# 95_RS485_RS232.net
KiCad netlist of a schematic drawn in Altium Designer
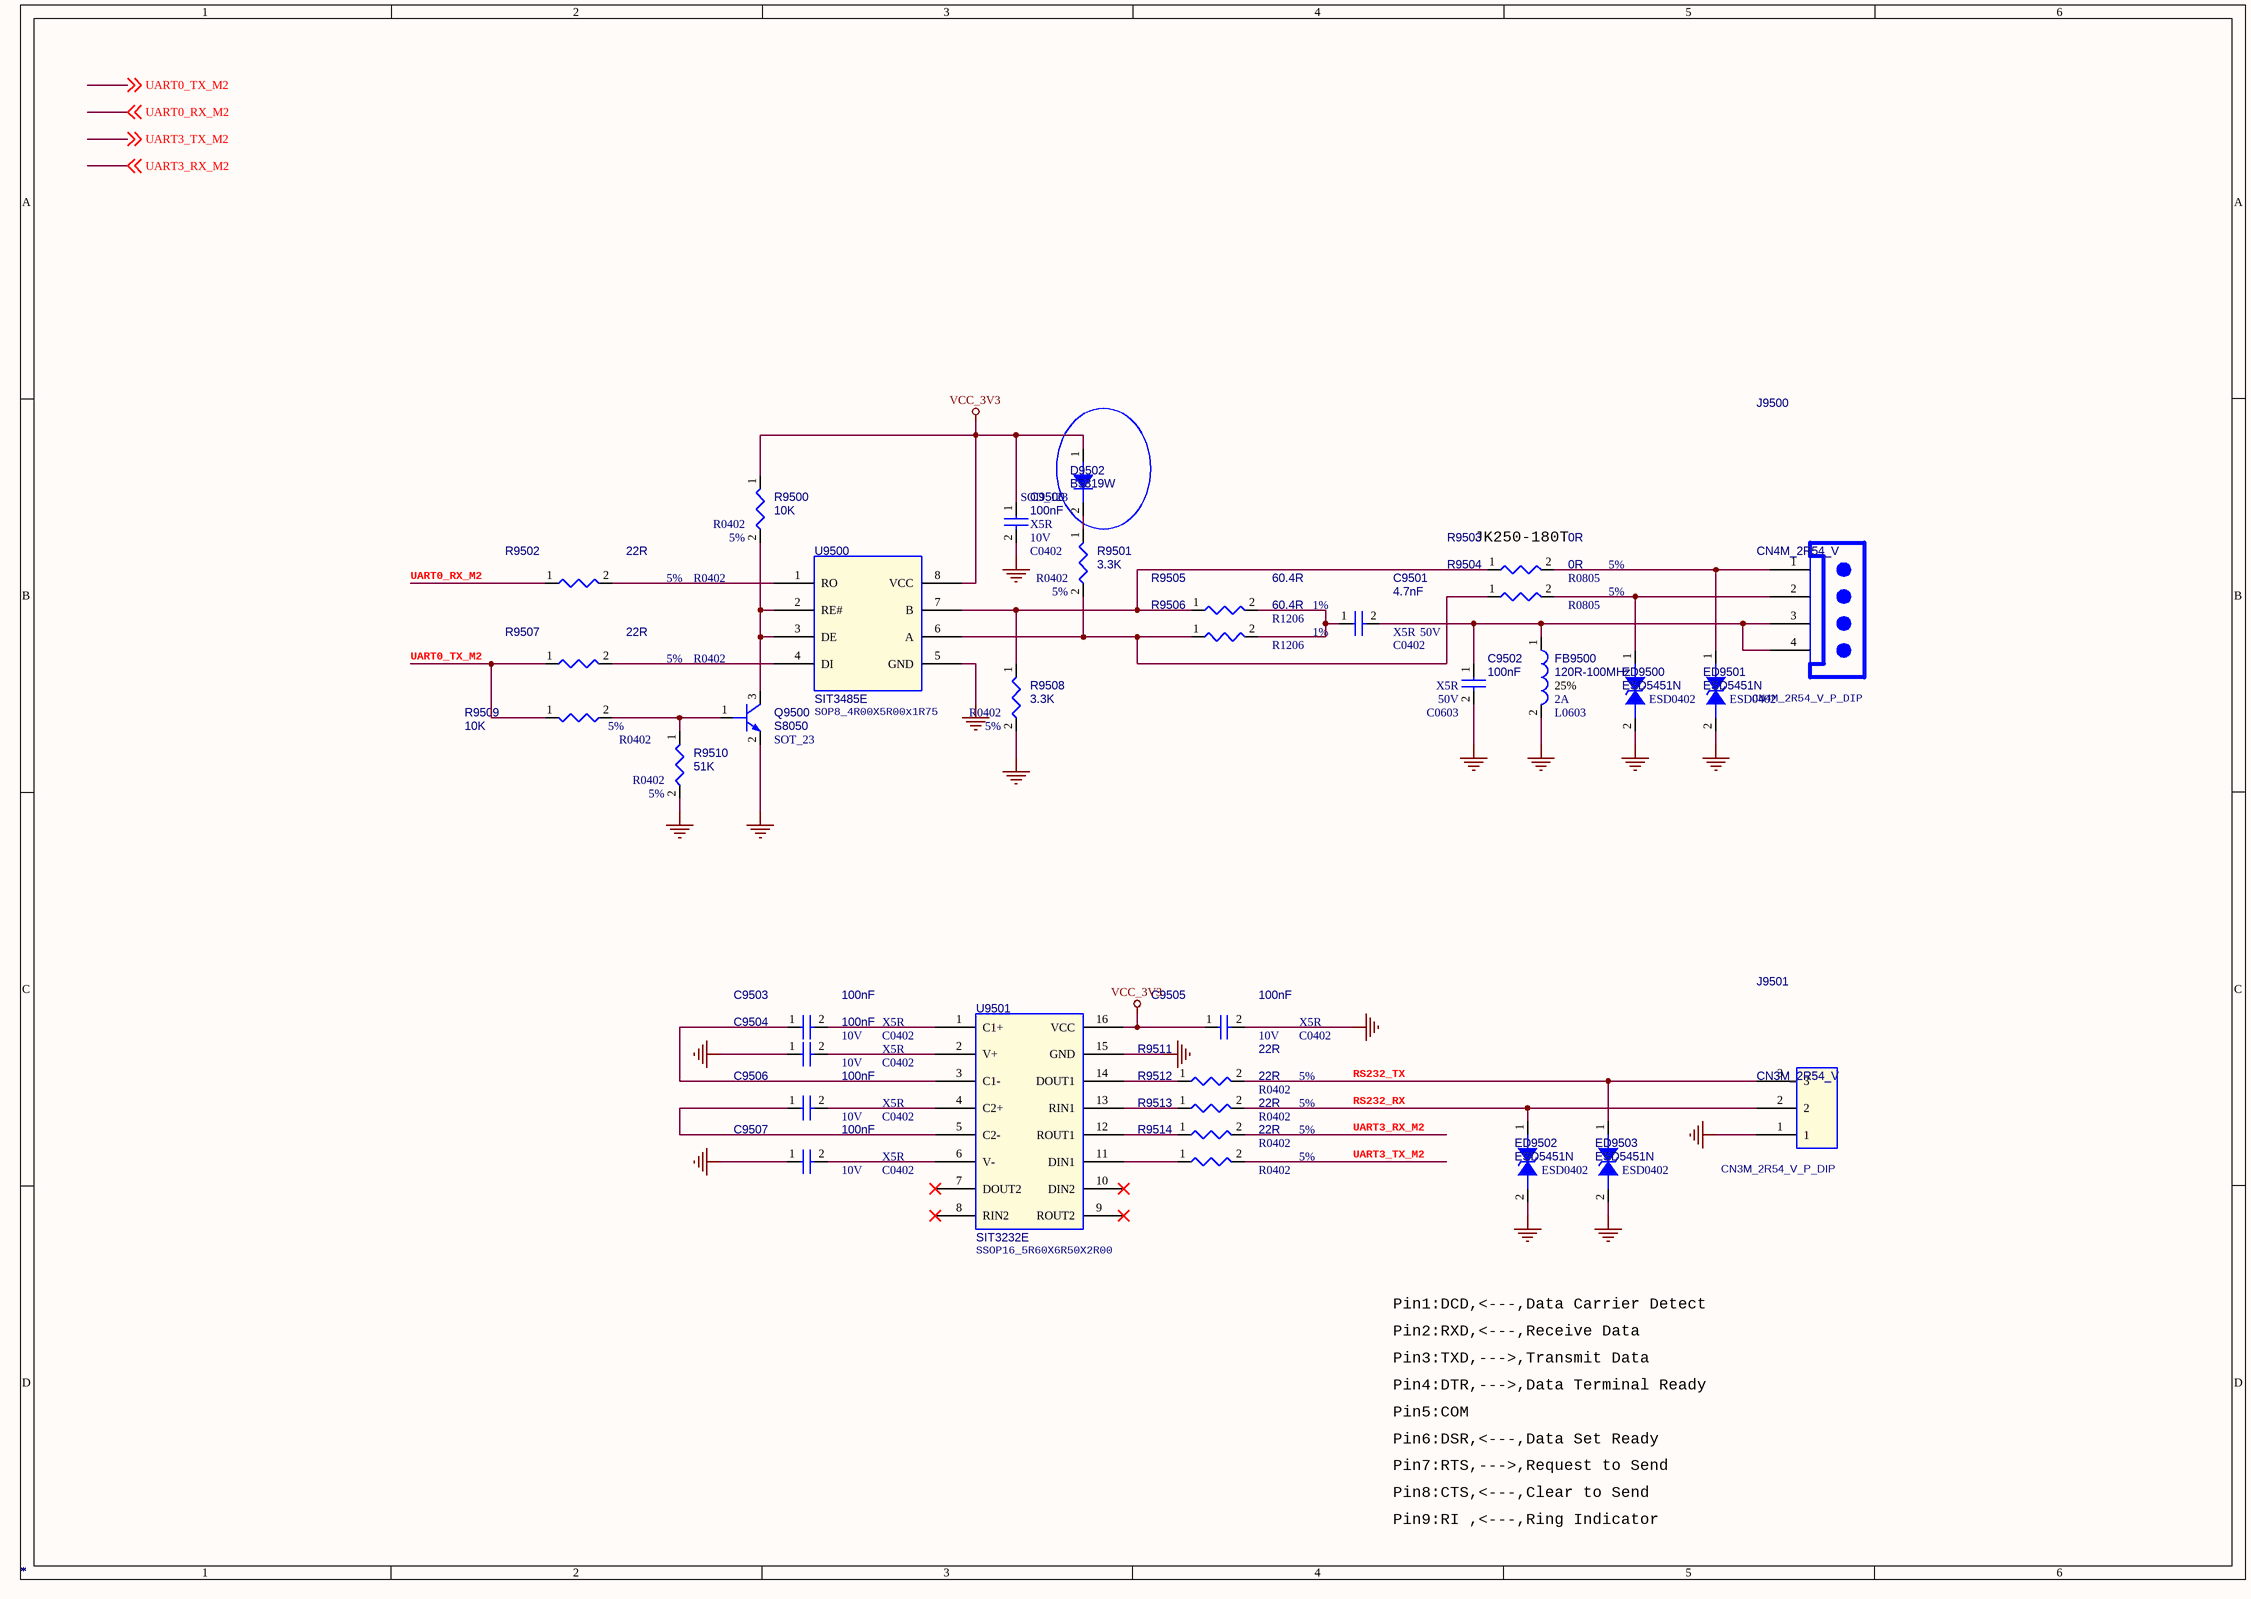
[diagram p0: 95.RS485_RS232.SchDoc]

(export (version "E")
  (design (tool "Eeschema 10.0.6"))
  (components
    (comp (ref "C9500")
      (value "*")
      (footprint "C0402")
      (description "cap,100.00nF,+/-10%,10V,X5R,C0402")
      (fields
        (field (name "VOLTAGE") "10V")
        (field (name "PCB FOOTPRINT") "C0402")
        (field (name "DIELECTRIC") "X5R")
        (field (name "MANUFACTURER") "TDK")
        (field (name "TOLERANCE") "10%")
        (field (name "ALTIUM_UNNAMED_1") "100nF")
        (field (name "CREATED BY") "JJJ")
      )
      (libsource (lib "*") (part "CAP NP"))
    )
    (comp (ref "C9501")
      (value "*")
      (footprint "C0402")
      (description "cap,4.70nF,+/-10%,50V,X5R,C0402")
      (fields
        (field (name "VOLTAGE") "50V")
        (field (name "PCB FOOTPRINT") "C0402")
        (field (name "DIELECTRIC") "X5R")
        (field (name "MANUFACTURER") "TDK")
        (field (name "TOLERANCE") "10%")
        (field (name "ALTIUM_UNNAMED_1") "4.7nF")
        (field (name "CREATED BY") "JJJ")
      )
      (libsource (lib "*") (part "CAP NP"))
    )
    (comp (ref "C9502")
      (value "*")
      (footprint "C0603")
      (description "cap,100.00nF,+/-10%,50V,X5R,C0603")
      (fields
        (field (name "VOLTAGE") "50V")
        (field (name "PCB FOOTPRINT") "C0603")
        (field (name "DIELECTRIC") "X5R")
        (field (name "TOLERANCE") "10%")
        (field (name "MANUFACTURER") "TDK")
        (field (name "ALTIUM_UNNAMED_1") "100nF")
        (field (name "CREATED BY") "JJJ")
      )
      (libsource (lib "*") (part "CAP NP"))
    )
    (comp (ref "C9503")
      (value "*")
      (footprint "C0402")
      (description "cap,100.00nF,+/-10%,10V,X5R,C0402")
      (fields
        (field (name "VOLTAGE") "10V")
        (field (name "PCB FOOTPRINT") "C0402")
        (field (name "DIELECTRIC") "X5R")
        (field (name "TOLERANCE") "10%")
        (field (name "MANUFACTURER") "TDK")
        (field (name "ALTIUM_UNNAMED_1") "100nF")
        (field (name "CREATED BY") "JJJ")
      )
      (libsource (lib "*") (part "CAP NP"))
    )
    (comp (ref "C9504")
      (value "*")
      (footprint "C0402")
      (description "cap,100.00nF,+/-10%,10V,X5R,C0402")
      (fields
        (field (name "VOLTAGE") "10V")
        (field (name "PCB FOOTPRINT") "C0402")
        (field (name "DIELECTRIC") "X5R")
        (field (name "TOLERANCE") "10%")
        (field (name "MANUFACTURER") "TDK")
        (field (name "ALTIUM_UNNAMED_1") "100nF")
        (field (name "CREATED BY") "JJJ")
      )
      (libsource (lib "*") (part "CAP NP"))
    )
    (comp (ref "C9505")
      (value "*")
      (footprint "C0402")
      (description "cap,100.00nF,+/-10%,10V,X5R,C0402")
      (fields
        (field (name "VOLTAGE") "10V")
        (field (name "PCB FOOTPRINT") "C0402")
        (field (name "DIELECTRIC") "X5R")
        (field (name "TOLERANCE") "10%")
        (field (name "MANUFACTURER") "TDK")
        (field (name "ALTIUM_UNNAMED_1") "100nF")
        (field (name "CREATED BY") "JJJ")
      )
      (libsource (lib "*") (part "CAP NP"))
    )
    (comp (ref "C9506")
      (value "*")
      (footprint "C0402")
      (description "cap,100.00nF,+/-10%,10V,X5R,C0402")
      (fields
        (field (name "VOLTAGE") "10V")
        (field (name "PCB FOOTPRINT") "C0402")
        (field (name "DIELECTRIC") "X5R")
        (field (name "TOLERANCE") "10%")
        (field (name "MANUFACTURER") "TDK")
        (field (name "ALTIUM_UNNAMED_1") "100nF")
        (field (name "CREATED BY") "JJJ")
      )
      (libsource (lib "*") (part "CAP NP"))
    )
    (comp (ref "C9507")
      (value "*")
      (footprint "C0402")
      (description "cap,100.00nF,+/-10%,10V,X5R,C0402")
      (fields
        (field (name "VOLTAGE") "10V")
        (field (name "PCB FOOTPRINT") "C0402")
        (field (name "DIELECTRIC") "X5R")
        (field (name "MANUFACTURER") "TDK")
        (field (name "TOLERANCE") "10%")
        (field (name "ALTIUM_UNNAMED_1") "100nF")
        (field (name "CREATED BY") "JJJ")
      )
      (libsource (lib "*") (part "CAP NP"))
    )
    (comp (ref "D9502")
      (value "*")
      (footprint "SOD_123")
      (description "Schottky BarrierЈ¬B5819W SOD-123")
      (fields
        (field (name "PCB FOOTPRINT") "SOD_123")
        (field (name "MANUFACTURER") "і¤µз")
        (field (name "ALTIUM_UNNAMED_1") "B5819W")
        (field (name "CREATED BY") "JJJ")
      )
      (libsource (lib "*") (part "DIODE"))
    )
    (comp (ref "ED9500")
      (value "*")
      (footprint "ESD0402")
      (description "1-Line, Bi-directional, Transient Voltage Suppressors.17.5pF.")
      (fields
        (field (name "PCB FOOTPRINT") "ESD0402")
        (field (name "MANUFACTURER") "WillSemi(О¤¶ы°лµјМе)")
        (field (name "ALTIUM_UNNAMED_1") "ESD5451N")
        (field (name "CREATED BY") "JJJ")
      )
      (libsource (lib "*") (part "DIODE BI_DIR TRIG"))
    )
    (comp (ref "ED9501")
      (value "*")
      (footprint "ESD0402")
      (description "1-Line, Bi-directional, Transient Voltage Suppressors.17.5pF.")
      (fields
        (field (name "PCB FOOTPRINT") "ESD0402")
        (field (name "MANUFACTURER") "WillSemi(О¤¶ы°лµјМе)")
        (field (name "ALTIUM_UNNAMED_1") "ESD5451N")
        (field (name "CREATED BY") "JJJ")
      )
      (libsource (lib "*") (part "DIODE BI_DIR TRIG"))
    )
    (comp (ref "ED9502")
      (value "*")
      (footprint "ESD0402")
      (description "1-Line, Bi-directional, Transient Voltage Suppressors.17.5pF.")
      (fields
        (field (name "PCB FOOTPRINT") "ESD0402")
        (field (name "MANUFACTURER") "WillSemi(О¤¶ы°лµјМе)")
        (field (name "ALTIUM_UNNAMED_1") "ESD5451N")
        (field (name "CREATED BY") "JJJ")
      )
      (libsource (lib "*") (part "DIODE BI_DIR TRIG"))
    )
    (comp (ref "ED9503")
      (value "*")
      (footprint "ESD0402")
      (description "1-Line, Bi-directional, Transient Voltage Suppressors.17.5pF.")
      (fields
        (field (name "PCB FOOTPRINT") "ESD0402")
        (field (name "MANUFACTURER") "WillSemi(О¤¶ы°лµјМе)")
        (field (name "ALTIUM_UNNAMED_1") "ESD5451N")
        (field (name "CREATED BY") "JJJ")
      )
      (libsource (lib "*") (part "DIODE BI_DIR TRIG"))
    )
    (comp (ref "FB9500")
      (value "*")
      (footprint "L0603")
      (description "BEAD,120R@100MHz,current=2000mA,0603")
      (fields
        (field (name "TOLERANCE") "25%")
        (field (name "PCB FOOTPRINT") "L0603")
        (field (name "IRMS") "2A")
        (field (name "MANUFACTURER") "Murata")
        (field (name "ALTIUM_UNNAMED_1") "120R-100MHz")
        (field (name "CREATED BY") "DZS")
      )
      (libsource (lib "*") (part "BEAD"))
    )
    (comp (ref "J9500")
      (value "*")
      (footprint "CN4M_2R54_V_P_DIP")
      (fields
        (field (name "PCB FOOTPRINT") "CN4M_2R54_V_P_DIP")
        (field (name "ALTIUM_UNNAMED_1") "CN4M_2R54_V")
      )
      (libsource (lib "*") (part "CON4_0"))
    )
    (comp (ref "J9501")
      (value "*")
      (footprint "DIP3_1X3_2R54")
      (description "µҐЕЕ3PINЈЁјдѕа2.54mmЈ©І»ґш·А»¤ЗЅµДІеХл")
      (fields
        (field (name "PCB FOOTPRINT") "CN3M_2R54_V_P_DIP")
        (field (name "MANUFACTURER PART NUMBER") "CON3M_1X3_2R54_V")
        (field (name "MANUFACTURER") "НъїЖґп")
        (field (name "ALTIUM_UNNAMED_1") "CN3M_2R54_V")
        (field (name "CREATED BY") "JJJ")
      )
      (libsource (lib "*") (part "CON3_1X3"))
    )
    (comp (ref "Q9500")
      (value "*")
      (footprint "SOT_23")
      (description "S8050,SOT23")
      (fields
        (field (name "PCB FOOTPRINT") "SOT_23")
        (field (name "MANUFACTURER") "і¤µз")
        (field (name "ALTIUM_UNNAMED_1") "S8050")
        (field (name "CREATED BY") "JJJ")
      )
      (libsource (lib "*") (part "NPN"))
    )
    (comp (ref "R9500")
      (value "*")
      (footprint "R0402")
      (description "НЁУГєсД¤µзЧи,10K,+/-5%,R0402,1/16W.")
      (fields
        (field (name "PCB FOOTPRINT") "R0402")
        (field (name "TOLERANCE") "5%")
        (field (name "MANUFACTURER") "YAGEO")
        (field (name "ALTIUM_UNNAMED_1") "10K")
        (field (name "CREATED BY") "YTL")
      )
      (libsource (lib "*") (part "RESISTOR_Dup1"))
    )
    (comp (ref "R9501")
      (value "*")
      (footprint "R0402")
      (description "НЁУГєсД¤µзЧи,3K3,+/-5%,R0402,1/16W.")
      (fields
        (field (name "PCB FOOTPRINT") "R0402")
        (field (name "TOLERANCE") "5%")
        (field (name "MANUFACTURER") "YAGEO")
        (field (name "ALTIUM_UNNAMED_1") "3.3K")
        (field (name "CREATED BY") "YTL")
      )
      (libsource (lib "*") (part "RESISTOR_Dup1"))
    )
    (comp (ref "R9502")
      (value "*")
      (footprint "R0402")
      (description "НЁУГєсД¤µзЧи,22R,+/-5%,R0402,1/16W.")
      (fields
        (field (name "PCB FOOTPRINT") "R0402")
        (field (name "TOLERANCE") "5%")
        (field (name "MANUFACTURER") "YAGEO")
        (field (name "ALTIUM_UNNAMED_1") "22R")
        (field (name "CREATED BY") "YTL")
      )
      (libsource (lib "*") (part "RESISTOR_Dup1"))
    )
    (comp (ref "R9503")
      (value "*")
      (footprint "R0402")
      (description "НЁУГєсД¤µзЧи,0R,+/-5%,R0805,1/8W.")
      (fields
        (field (name "PCB FOOTPRINT") "R0805")
        (field (name "TOLERANCE") "5%")
        (field (name "MANUFACTURER") "YAGEO")
        (field (name "ALTIUM_UNNAMED_1") "0R")
        (field (name "CREATED BY") "YTL")
      )
      (libsource (lib "*") (part "RESISTOR_Dup1"))
    )
    (comp (ref "R9504")
      (value "*")
      (footprint "R0402")
      (description "НЁУГєсД¤µзЧи,0R,+/-5%,R0805,1/8W.")
      (fields
        (field (name "PCB FOOTPRINT") "R0805")
        (field (name "TOLERANCE") "5%")
        (field (name "MANUFACTURER") "YAGEO")
        (field (name "ALTIUM_UNNAMED_1") "0R")
        (field (name "CREATED BY") "YTL")
      )
      (libsource (lib "*") (part "RESISTOR_Dup1"))
    )
    (comp (ref "R9505")
      (value "*")
      (footprint "R0402")
      (description "НЁУГєсД¤µзЧи,60R4,+/-1%,R1206,1/4W.")
      (fields
        (field (name "PCB FOOTPRINT") "R1206")
        (field (name "TOLERANCE") "1%")
        (field (name "MANUFACTURER") "YAGEO")
        (field (name "ALTIUM_UNNAMED_1") "60.4R")
        (field (name "CREATED BY") "YTL")
      )
      (libsource (lib "*") (part "RESISTOR_Dup1"))
    )
    (comp (ref "R9506")
      (value "*")
      (footprint "R0402")
      (description "НЁУГєсД¤µзЧи,60R4,+/-1%,R1206,1/4W.")
      (fields
        (field (name "PCB FOOTPRINT") "R1206")
        (field (name "TOLERANCE") "1%")
        (field (name "MANUFACTURER") "YAGEO")
        (field (name "ALTIUM_UNNAMED_1") "60.4R")
        (field (name "CREATED BY") "YTL")
      )
      (libsource (lib "*") (part "RESISTOR_Dup1"))
    )
    (comp (ref "R9507")
      (value "*")
      (footprint "R0402")
      (description "НЁУГєсД¤µзЧи,22R,+/-5%,R0402,1/16W.")
      (fields
        (field (name "PCB FOOTPRINT") "R0402")
        (field (name "TOLERANCE") "5%")
        (field (name "MANUFACTURER") "YAGEO")
        (field (name "ALTIUM_UNNAMED_1") "22R")
        (field (name "CREATED BY") "YTL")
      )
      (libsource (lib "*") (part "RESISTOR_Dup1"))
    )
    (comp (ref "R9508")
      (value "*")
      (footprint "R0402")
      (description "НЁУГєсД¤µзЧи,3K3,+/-5%,R0402,1/16W.")
      (fields
        (field (name "PCB FOOTPRINT") "R0402")
        (field (name "TOLERANCE") "5%")
        (field (name "MANUFACTURER") "YAGEO")
        (field (name "ALTIUM_UNNAMED_1") "3.3K")
        (field (name "CREATED BY") "YTL")
      )
      (libsource (lib "*") (part "RESISTOR_Dup1"))
    )
    (comp (ref "R9509")
      (value "*")
      (footprint "R0402")
      (description "НЁУГєсД¤µзЧи,10K,+/-5%,R0402,1/16W.")
      (fields
        (field (name "PCB FOOTPRINT") "R0402")
        (field (name "TOLERANCE") "5%")
        (field (name "MANUFACTURER") "YAGEO")
        (field (name "ALTIUM_UNNAMED_1") "10K")
        (field (name "CREATED BY") "YTL")
      )
      (libsource (lib "*") (part "RESISTOR_Dup1"))
    )
    (comp (ref "R9510")
      (value "*")
      (footprint "R0402")
      (description "НЁУГєсД¤µзЧи,51K,+/-5%,R0402,1/16W.")
      (fields
        (field (name "PCB FOOTPRINT") "R0402")
        (field (name "TOLERANCE") "5%")
        (field (name "MANUFACTURER") "YAGEO")
        (field (name "ALTIUM_UNNAMED_1") "51K")
        (field (name "CREATED BY") "YTL")
      )
      (libsource (lib "*") (part "RESISTOR_Dup1"))
    )
    (comp (ref "R9511")
      (value "*")
      (footprint "R0402")
      (description "НЁУГєсД¤µзЧи,22R,+/-5%,R0402,1/16W.")
      (fields
        (field (name "PCB FOOTPRINT") "R0402")
        (field (name "TOLERANCE") "5%")
        (field (name "MANUFACTURER") "YAGEO")
        (field (name "ALTIUM_UNNAMED_1") "22R")
        (field (name "CREATED BY") "YTL")
      )
      (libsource (lib "*") (part "RESISTOR_Dup1"))
    )
    (comp (ref "R9512")
      (value "*")
      (footprint "R0402")
      (description "НЁУГєсД¤µзЧи,22R,+/-5%,R0402,1/16W.")
      (fields
        (field (name "PCB FOOTPRINT") "R0402")
        (field (name "TOLERANCE") "5%")
        (field (name "MANUFACTURER") "YAGEO")
        (field (name "ALTIUM_UNNAMED_1") "22R")
        (field (name "CREATED BY") "YTL")
      )
      (libsource (lib "*") (part "RESISTOR_Dup1"))
    )
    (comp (ref "R9513")
      (value "*")
      (footprint "R0402")
      (description "НЁУГєсД¤µзЧи,22R,+/-5%,R0402,1/16W.")
      (fields
        (field (name "PCB FOOTPRINT") "R0402")
        (field (name "TOLERANCE") "5%")
        (field (name "MANUFACTURER") "YAGEO")
        (field (name "ALTIUM_UNNAMED_1") "22R")
        (field (name "CREATED BY") "YTL")
      )
      (libsource (lib "*") (part "RESISTOR_Dup1"))
    )
    (comp (ref "R9514")
      (value "*")
      (footprint "R0402")
      (description "НЁУГєсД¤µзЧи,22R,+/-5%,R0402,1/16W.")
      (fields
        (field (name "PCB FOOTPRINT") "R0402")
        (field (name "TOLERANCE") "5%")
        (field (name "MANUFACTURER") "YAGEO")
        (field (name "ALTIUM_UNNAMED_1") "22R")
        (field (name "CREATED BY") "YTL")
      )
      (libsource (lib "*") (part "RESISTOR_Dup1"))
    )
    (comp (ref "U9500")
      (value "*")
      (footprint "SOP8_4R00X5R00x1R75")
      (fields
        (field (name "PCB FOOTPRINT") "SOP8_4R00X5R00x1R75")
        (field (name "ALTIUM_UNNAMED_1") "SIT3485E")
      )
      (libsource (lib "*") (part "MAX3485_0"))
    )
    (comp (ref "U9501")
      (value "*")
      (footprint "SOP16")
      (fields
        (field (name "PCB FOOTPRINT") "SSOP16_5R60X6R50X2R00")
        (field (name "ALTIUM_UNNAMED_1") "SIT3232E")
      )
      (libsource (lib "*") (part "MAX3232/SIT3232E"))
    )
  )
  (nets
    (net (code "1") (name "/RS232_RX") (class "Default")
      (node (ref "ED9502") (pin "1") (pinfunction "1_1") (pintype "passive"))
      (node (ref "J9501") (pin "2") (pinfunction "2_2") (pintype "passive"))
      (node (ref "R9512") (pin "2") (pinfunction "2_2") (pintype "passive"))
    )
    (net (code "2") (name "/RS232_TX") (class "Default")
      (node (ref "ED9503") (pin "1") (pinfunction "1_1") (pintype "passive"))
      (node (ref "J9501") (pin "3") (pinfunction "3_3") (pintype "passive"))
      (node (ref "R9511") (pin "2") (pinfunction "2_2") (pintype "passive"))
    )
    (net (code "3") (name "GND") (class "Default")
      (node (ref "C9500") (pin "2") (pinfunction "2_2") (pintype "passive"))
      (node (ref "C9502") (pin "2") (pinfunction "2_2") (pintype "passive"))
      (node (ref "C9504") (pin "1") (pinfunction "1_1") (pintype "passive"))
      (node (ref "C9505") (pin "2") (pinfunction "2_2") (pintype "passive"))
      (node (ref "C9507") (pin "1") (pinfunction "1_1") (pintype "passive"))
      (node (ref "ED9500") (pin "2") (pinfunction "2_2") (pintype "passive"))
      (node (ref "ED9501") (pin "2") (pinfunction "2_2") (pintype "passive"))
      (node (ref "ED9502") (pin "2") (pinfunction "2_2") (pintype "passive"))
      (node (ref "ED9503") (pin "2") (pinfunction "2_2") (pintype "passive"))
      (node (ref "FB9500") (pin "2") (pinfunction "2_2") (pintype "passive"))
      (node (ref "J9501") (pin "1") (pinfunction "1_1") (pintype "passive"))
      (node (ref "Q9500") (pin "2") (pinfunction "EMITTER_2") (pintype "passive"))
      (node (ref "R9508") (pin "2") (pinfunction "2_2") (pintype "passive"))
      (node (ref "R9510") (pin "2") (pinfunction "2_2") (pintype "passive"))
      (node (ref "U9500") (pin "5") (pinfunction "GND_5") (pintype "passive"))
      (node (ref "U9501") (pin "15") (pinfunction "GND_15") (pintype "passive"))
    )
    (net (code "4") (name "Net-(C9501-Pad1)") (class "Default")
      (node (ref "C9501") (pin "1") (pinfunction "1_1") (pintype "passive"))
      (node (ref "R9505") (pin "2") (pinfunction "2_2") (pintype "passive"))
      (node (ref "R9506") (pin "2") (pinfunction "2_2") (pintype "passive"))
    )
    (net (code "5") (name "Net-(D9502-K)") (class "Default")
      (node (ref "D9502") (pin "2") (pinfunction "K_2") (pintype "passive"))
      (node (ref "R9501") (pin "1") (pinfunction "1_1") (pintype "passive"))
    )
    (net (code "6") (name "Net-(J9500-3V3)") (class "Default")
      (node (ref "C9501") (pin "2") (pinfunction "2_2") (pintype "passive"))
      (node (ref "C9502") (pin "1") (pinfunction "1_1") (pintype "passive"))
      (node (ref "FB9500") (pin "1") (pinfunction "1_1") (pintype "passive"))
      (node (ref "J9500") (pin "3") (pinfunction "TX_3") (pintype "passive"))
      (node (ref "J9500") (pin "4") (pinfunction "3V3_4") (pintype "passive"))
    )
    (net (code "7") (name "Net-(J9500-GND)") (class "Default")
      (node (ref "ED9501") (pin "1") (pinfunction "1_1") (pintype "passive"))
      (node (ref "J9500") (pin "1") (pinfunction "GND_1") (pintype "passive"))
      (node (ref "R9503") (pin "2") (pinfunction "2_2") (pintype "passive"))
    )
    (net (code "8") (name "Net-(J9500-RX)") (class "Default")
      (node (ref "ED9500") (pin "1") (pinfunction "1_1") (pintype "passive"))
      (node (ref "J9500") (pin "2") (pinfunction "RX_2") (pintype "passive"))
      (node (ref "R9504") (pin "2") (pinfunction "2_2") (pintype "passive"))
    )
    (net (code "9") (name "Net-(Q9500-BASE)") (class "Default")
      (node (ref "Q9500") (pin "1") (pinfunction "BASE_1") (pintype "passive"))
      (node (ref "R9509") (pin "2") (pinfunction "2_2") (pintype "passive"))
      (node (ref "R9510") (pin "1") (pinfunction "1_1") (pintype "passive"))
    )
    (net (code "10") (name "Net-(Q9500-COLLECTOR)") (class "Default")
      (node (ref "Q9500") (pin "3") (pinfunction "COLLECTOR_3") (pintype "passive"))
      (node (ref "R9500") (pin "2") (pinfunction "2_2") (pintype "passive"))
      (node (ref "U9500") (pin "2") (pinfunction "RE#_2") (pintype "passive"))
      (node (ref "U9500") (pin "3") (pinfunction "DE_3") (pintype "passive"))
    )
    (net (code "11") (name "Net-(U9500-A)") (class "Default")
      (node (ref "R9501") (pin "2") (pinfunction "2_2") (pintype "passive"))
      (node (ref "R9504") (pin "1") (pinfunction "1_1") (pintype "passive"))
      (node (ref "R9506") (pin "1") (pinfunction "1_1") (pintype "passive"))
      (node (ref "U9500") (pin "6") (pinfunction "A_6") (pintype "passive"))
    )
    (net (code "12") (name "Net-(U9500-B)") (class "Default")
      (node (ref "R9503") (pin "1") (pinfunction "1_1") (pintype "passive"))
      (node (ref "R9505") (pin "1") (pinfunction "1_1") (pintype "passive"))
      (node (ref "R9508") (pin "1") (pinfunction "1_1") (pintype "passive"))
      (node (ref "U9500") (pin "7") (pinfunction "B_7") (pintype "passive"))
    )
    (net (code "13") (name "Net-(U9500-DI)") (class "Default")
      (node (ref "R9507") (pin "2") (pinfunction "2_2") (pintype "passive"))
      (node (ref "U9500") (pin "4") (pinfunction "DI_4") (pintype "passive"))
    )
    (net (code "14") (name "Net-(U9500-RO)") (class "Default")
      (node (ref "R9502") (pin "2") (pinfunction "2_2") (pintype "passive"))
      (node (ref "U9500") (pin "1") (pinfunction "RO_1") (pintype "passive"))
    )
    (net (code "15") (name "Net-(U9501-C1+)") (class "Default")
      (node (ref "C9503") (pin "2") (pinfunction "2_2") (pintype "passive"))
      (node (ref "U9501") (pin "1") (pinfunction "C1+_1") (pintype "passive"))
    )
    (net (code "16") (name "Net-(U9501-C1-)") (class "Default")
      (node (ref "C9503") (pin "1") (pinfunction "1_1") (pintype "passive"))
      (node (ref "U9501") (pin "3") (pinfunction "C1-_3") (pintype "passive"))
    )
    (net (code "17") (name "Net-(U9501-C2+)") (class "Default")
      (node (ref "C9506") (pin "2") (pinfunction "2_2") (pintype "passive"))
      (node (ref "U9501") (pin "4") (pinfunction "C2+_4") (pintype "passive"))
    )
    (net (code "18") (name "Net-(U9501-C2-)") (class "Default")
      (node (ref "C9506") (pin "1") (pinfunction "1_1") (pintype "passive"))
      (node (ref "U9501") (pin "5") (pinfunction "C2-_5") (pintype "passive"))
    )
    (net (code "19") (name "Net-(U9501-DIN1)") (class "Default")
      (node (ref "R9514") (pin "1") (pinfunction "1_1") (pintype "passive"))
      (node (ref "U9501") (pin "11") (pinfunction "DIN1_11") (pintype "passive"))
    )
    (net (code "20") (name "Net-(U9501-DOUT1)") (class "Default")
      (node (ref "R9511") (pin "1") (pinfunction "1_1") (pintype "passive"))
      (node (ref "U9501") (pin "14") (pinfunction "DOUT1_14") (pintype "passive"))
    )
    (net (code "21") (name "Net-(U9501-RIN1)") (class "Default")
      (node (ref "R9512") (pin "1") (pinfunction "1_1") (pintype "passive"))
      (node (ref "U9501") (pin "13") (pinfunction "RIN1_13") (pintype "passive"))
    )
    (net (code "22") (name "Net-(U9501-ROUT1)") (class "Default")
      (node (ref "R9513") (pin "1") (pinfunction "1_1") (pintype "passive"))
      (node (ref "U9501") (pin "12") (pinfunction "ROUT1_12") (pintype "passive"))
    )
    (net (code "23") (name "Net-(U9501-V+)") (class "Default")
      (node (ref "C9504") (pin "2") (pinfunction "2_2") (pintype "passive"))
      (node (ref "U9501") (pin "2") (pinfunction "V+_2") (pintype "passive"))
    )
    (net (code "24") (name "Net-(U9501-V-)") (class "Default")
      (node (ref "C9507") (pin "2") (pinfunction "2_2") (pintype "passive"))
      (node (ref "U9501") (pin "6") (pinfunction "V-_6") (pintype "passive"))
    )
    (net (code "25") (name "UART0_RX_M2") (class "Default")
      (node (ref "R9502") (pin "1") (pinfunction "1_1") (pintype "passive"))
    )
    (net (code "26") (name "UART0_TX_M2") (class "Default")
      (node (ref "R9507") (pin "1") (pinfunction "1_1") (pintype "passive"))
      (node (ref "R9509") (pin "1") (pinfunction "1_1") (pintype "passive"))
    )
    (net (code "27") (name "UART3_RX_M2") (class "Default")
      (node (ref "R9513") (pin "2") (pinfunction "2_2") (pintype "passive"))
    )
    (net (code "28") (name "UART3_TX_M2") (class "Default")
      (node (ref "R9514") (pin "2") (pinfunction "2_2") (pintype "passive"))
    )
    (net (code "29") (name "VCC_3V3") (class "Default")
      (node (ref "C9500") (pin "1") (pinfunction "1_1") (pintype "passive"))
      (node (ref "C9505") (pin "1") (pinfunction "1_1") (pintype "passive"))
      (node (ref "D9502") (pin "1") (pinfunction "A_1") (pintype "passive"))
      (node (ref "R9500") (pin "1") (pinfunction "1_1") (pintype "passive"))
      (node (ref "U9500") (pin "8") (pinfunction "VCC_8") (pintype "passive"))
      (node (ref "U9501") (pin "16") (pinfunction "VCC_16") (pintype "passive"))
    )
    (net (code "30") (name "unconnected-(U9501-DIN2-Pad10)") (class "Default")
      (node (ref "U9501") (pin "10") (pinfunction "DIN2_10") (pintype "passive+no_connect"))
    )
    (net (code "31") (name "unconnected-(U9501-DOUT2-Pad7)") (class "Default")
      (node (ref "U9501") (pin "7") (pinfunction "DOUT2_7") (pintype "passive+no_connect"))
    )
    (net (code "32") (name "unconnected-(U9501-RIN2-Pad8)") (class "Default")
      (node (ref "U9501") (pin "8") (pinfunction "RIN2_8") (pintype "passive+no_connect"))
    )
    (net (code "33") (name "unconnected-(U9501-ROUT2-Pad9)") (class "Default")
      (node (ref "U9501") (pin "9") (pinfunction "ROUT2_9") (pintype "passive+no_connect"))
    )
  )
)
